# RF-input-bandpass.net
KiCad netlist of a schematic drawn in EAGLE
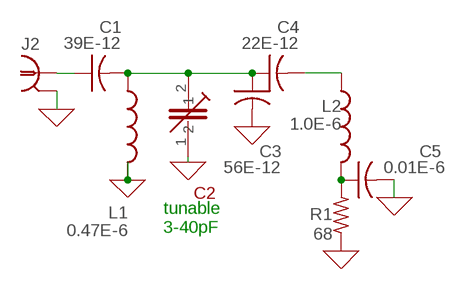
[diagram p0: schematic, sheet 1]

(export (version "E")
  (design (tool "Eeschema 10.0.6"))
  (components
    (comp (ref "C1")
      (value "39E-12")
      (footprint "eagle-import:C025-024X044")
      (libsource (lib "eagle-import") (part "C-US025-024X044"))
    )
    (comp (ref "C2")
      (value "4.6E-12")
      (footprint "eagle-import:10_MM_TOP_BOTTOM_3_LEAD_STD")
      (fields (field (name "SPICEPREFIX") "C"))
      (libsource (lib "eagle-import") (part "GYC20000"))
    )
    (comp (ref "C3")
      (value "56E-12")
      (footprint "eagle-import:C025-024X044")
      (libsource (lib "eagle-import") (part "C-US025-024X044"))
    )
    (comp (ref "C4")
      (value "22E-12")
      (footprint "eagle-import:C025-024X044")
      (libsource (lib "eagle-import") (part "C-US025-024X044"))
    )
    (comp (ref "C5")
      (value "0.01E-6")
      (footprint "eagle-import:C025-024X044")
      (libsource (lib "eagle-import") (part "C-US025-024X044"))
    )
    (comp (ref "J2")
      (value "DC 0 AC 1E-6")
      (footprint "eagle-import:R141426")
      (fields
        (field (name "MF") "FARNELL")
        (field (name "MPN") "R141426161")
        (field (name "SPICEPREFIX") "V")
      )
      (libsource (lib "eagle-import") (part "R141426"))
    )
    (comp (ref "L1")
      (value "0.47E-6")
      (footprint "eagle-import:0204_5")
      (libsource (lib "eagle-import") (part "L-US0204/5"))
    )
    (comp (ref "L2")
      (value "1.0E-6")
      (footprint "eagle-import:0204_5")
      (libsource (lib "eagle-import") (part "L-US0204/5"))
    )
    (comp (ref "R1")
      (value "68")
      (footprint "eagle-import:0204V")
      (fields (field (name "SPICEPREFIX") "R"))
      (libsource (lib "eagle-import") (part "R-US_0204/2V"))
    )
  )
  (nets
    (net (code "1") (name "GND") (class "Default")
      (node (ref "C2") (pin "1") (pinfunction "1_1") (pintype "passive"))
      (node (ref "C3") (pin "2") (pinfunction "2_2") (pintype "passive"))
      (node (ref "C5") (pin "2") (pinfunction "2_2") (pintype "passive"))
      (node (ref "J2") (pin "2") (pinfunction "2_2") (pintype "passive"))
      (node (ref "J2") (pin "3") (pinfunction "2_3") (pintype "passive"))
      (node (ref "J2") (pin "4") (pinfunction "2_4") (pintype "passive"))
      (node (ref "J2") (pin "5") (pinfunction "2_5") (pintype "passive"))
      (node (ref "L1") (pin "2") (pinfunction "2_2") (pintype "passive"))
      (node (ref "R1") (pin "1") (pinfunction "1_1") (pintype "passive"))
    )
    (net (code "2") (name "Net-(C1-Pad1)") (class "Default")
      (node (ref "C1") (pin "1") (pinfunction "1_1") (pintype "passive"))
      (node (ref "J2") (pin "1") (pinfunction "1_1") (pintype "passive"))
    )
    (net (code "3") (name "Net-(C1-Pad2)") (class "Default")
      (node (ref "C1") (pin "2") (pinfunction "2_2") (pintype "passive"))
      (node (ref "C2") (pin "2") (pinfunction "2_2") (pintype "passive"))
      (node (ref "C3") (pin "1") (pinfunction "1_1") (pintype "passive"))
      (node (ref "C4") (pin "1") (pinfunction "1_1") (pintype "passive"))
      (node (ref "L1") (pin "1") (pinfunction "1_1") (pintype "passive"))
    )
    (net (code "4") (name "Net-(C4-Pad2)") (class "Default")
      (node (ref "C4") (pin "2") (pinfunction "2_2") (pintype "passive"))
      (node (ref "L2") (pin "1") (pinfunction "1_1") (pintype "passive"))
    )
    (net (code "5") (name "Net-(C5-Pad1)") (class "Default")
      (node (ref "C5") (pin "1") (pinfunction "1_1") (pintype "passive"))
      (node (ref "L2") (pin "2") (pinfunction "2_2") (pintype "passive"))
      (node (ref "R1") (pin "2") (pinfunction "2_2") (pintype "passive"))
    )
  )
)
